# LT3470.net
KiCad netlist of a schematic drawn in Altium Designer
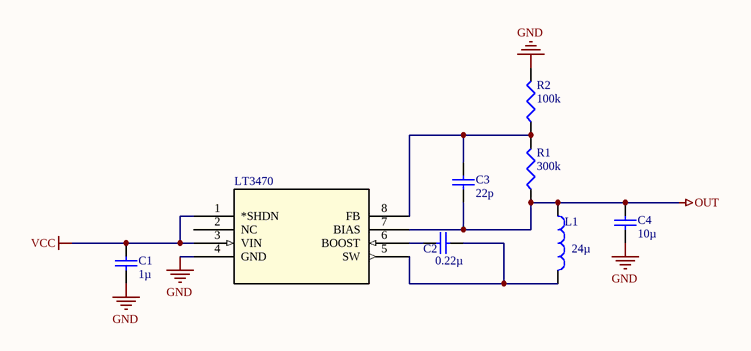
[diagram p0: LT3470.SchDoc]

(export (version "E")
  (design (tool "Eeschema 10.0.6"))
  (components
    (comp (ref "C1")
      (value "1µ")
      (footprint "CAPR2.54-5.1x3.2")
      (description "Condensateur")
      (fields (field (name "DESIGNER") "ECAM 2004"))
      (libsource (lib "LT3470") (part "Condensateur"))
    )
    (comp (ref "C2")
      (value "0.22µ")
      (footprint "CAPR2.54-5.1x3.2")
      (description "Condensateur")
      (fields (field (name "DESIGNER") "ECAM 2004"))
      (libsource (lib "LT3470") (part "Condensateur"))
    )
    (comp (ref "C3")
      (value "22p")
      (footprint "CAPR2.54-5.1x3.2")
      (description "Condensateur")
      (fields (field (name "DESIGNER") "ECAM 2004"))
      (libsource (lib "LT3470") (part "Condensateur"))
    )
    (comp (ref "C4")
      (value "10µ")
      (footprint "CAPR2.54-5.1x3.2")
      (description "Condensateur")
      (fields (field (name "DESIGNER") "ECAM 2004"))
      (libsource (lib "LT3470") (part "Condensateur"))
    )
    (comp (ref "L1")
      (value "24µ")
      (footprint "AXIAL-0.5")
      (description "Inductance")
      (fields (field (name "DESIGNER") "ECAM 2003"))
      (libsource (lib "LT3470") (part "Inductance"))
    )
    (comp (ref "LT3470")
      (value "Part Number: LT3470ITS8")
      (footprint "TSOT-23_TS8")
      (description "No Description Available")
      (fields
        (field (name "MANUFACTURER_PART_NUMBER") "LT3470ITS8")
        (field (name "COPYRIGHT") "Copyright (C) 2018 Accelerated Designs. All rights reserved")
      )
      (libsource (lib "LT3470") (part "LT3470ITS8"))
    )
    (comp (ref "R1")
      (value "300k")
      (footprint "AXIAL-0.4")
      (description "Résistance standard")
      (fields (field (name "Comment") "Résistance") (field (name "DESIGNER") "ECAM 2005"))
      (libsource (lib "LT3470") (part "Résistance"))
    )
    (comp (ref "R2")
      (value "100k")
      (footprint "AXIAL-0.4")
      (description "Résistance standard")
      (fields (field (name "Comment") "Résistance") (field (name "DESIGNER") "ECAM 2005"))
      (libsource (lib "LT3470") (part "Résistance"))
    )
  )
  (nets
    (net (code "1") (name "GND") (class "Default")
      (node (ref "C1") (pin "2") (pinfunction "2_2") (pintype "passive"))
      (node (ref "C4") (pin "2") (pinfunction "2_2") (pintype "passive"))
      (node (ref "LT3470") (pin "4") (pinfunction "GND_4") (pintype "power_in"))
      (node (ref "R2") (pin "2") (pinfunction "2_2") (pintype "passive"))
    )
    (net (code "2") (name "Net-(LT3470-BOOST)") (class "Default")
      (node (ref "C2") (pin "1") (pinfunction "1_1") (pintype "passive"))
      (node (ref "LT3470") (pin "6") (pinfunction "BOOST_6") (pintype "input"))
    )
    (net (code "3") (name "Net-(LT3470-FB)") (class "Default")
      (node (ref "C3") (pin "2") (pinfunction "2_2") (pintype "passive"))
      (node (ref "LT3470") (pin "8") (pinfunction "FB_8") (pintype "passive"))
      (node (ref "R1") (pin "2") (pinfunction "2_2") (pintype "passive"))
      (node (ref "R2") (pin "1") (pinfunction "1_1") (pintype "passive"))
    )
    (net (code "4") (name "Net-(LT3470-SW)") (class "Default")
      (node (ref "C2") (pin "2") (pinfunction "2_2") (pintype "passive"))
      (node (ref "L1") (pin "2") (pinfunction "2_2") (pintype "passive"))
      (node (ref "LT3470") (pin "5") (pinfunction "SW_5") (pintype "output"))
    )
    (net (code "5") (name "OUT") (class "Default")
      (node (ref "C3") (pin "1") (pinfunction "1_1") (pintype "passive"))
      (node (ref "C4") (pin "1") (pinfunction "1_1") (pintype "passive"))
      (node (ref "L1") (pin "1") (pinfunction "1_1") (pintype "passive"))
      (node (ref "LT3470") (pin "7") (pinfunction "BIAS_7") (pintype "passive"))
      (node (ref "R1") (pin "1") (pinfunction "1_1") (pintype "passive"))
    )
    (net (code "6") (name "VCC") (class "Default")
      (node (ref "C1") (pin "1") (pinfunction "1_1") (pintype "passive"))
      (node (ref "LT3470") (pin "1") (pinfunction "*SHDN_1") (pintype "passive"))
      (node (ref "LT3470") (pin "3") (pinfunction "VIN_3") (pintype "input"))
    )
    (net (code "7") (name "unconnected-(LT3470-NC-Pad2)") (class "Default")
      (node (ref "LT3470") (pin "2") (pinfunction "NC_2") (pintype "passive"))
    )
  )
)
